# Power_Supply_Board.net
KiCad netlist of a schematic drawn in EAGLE
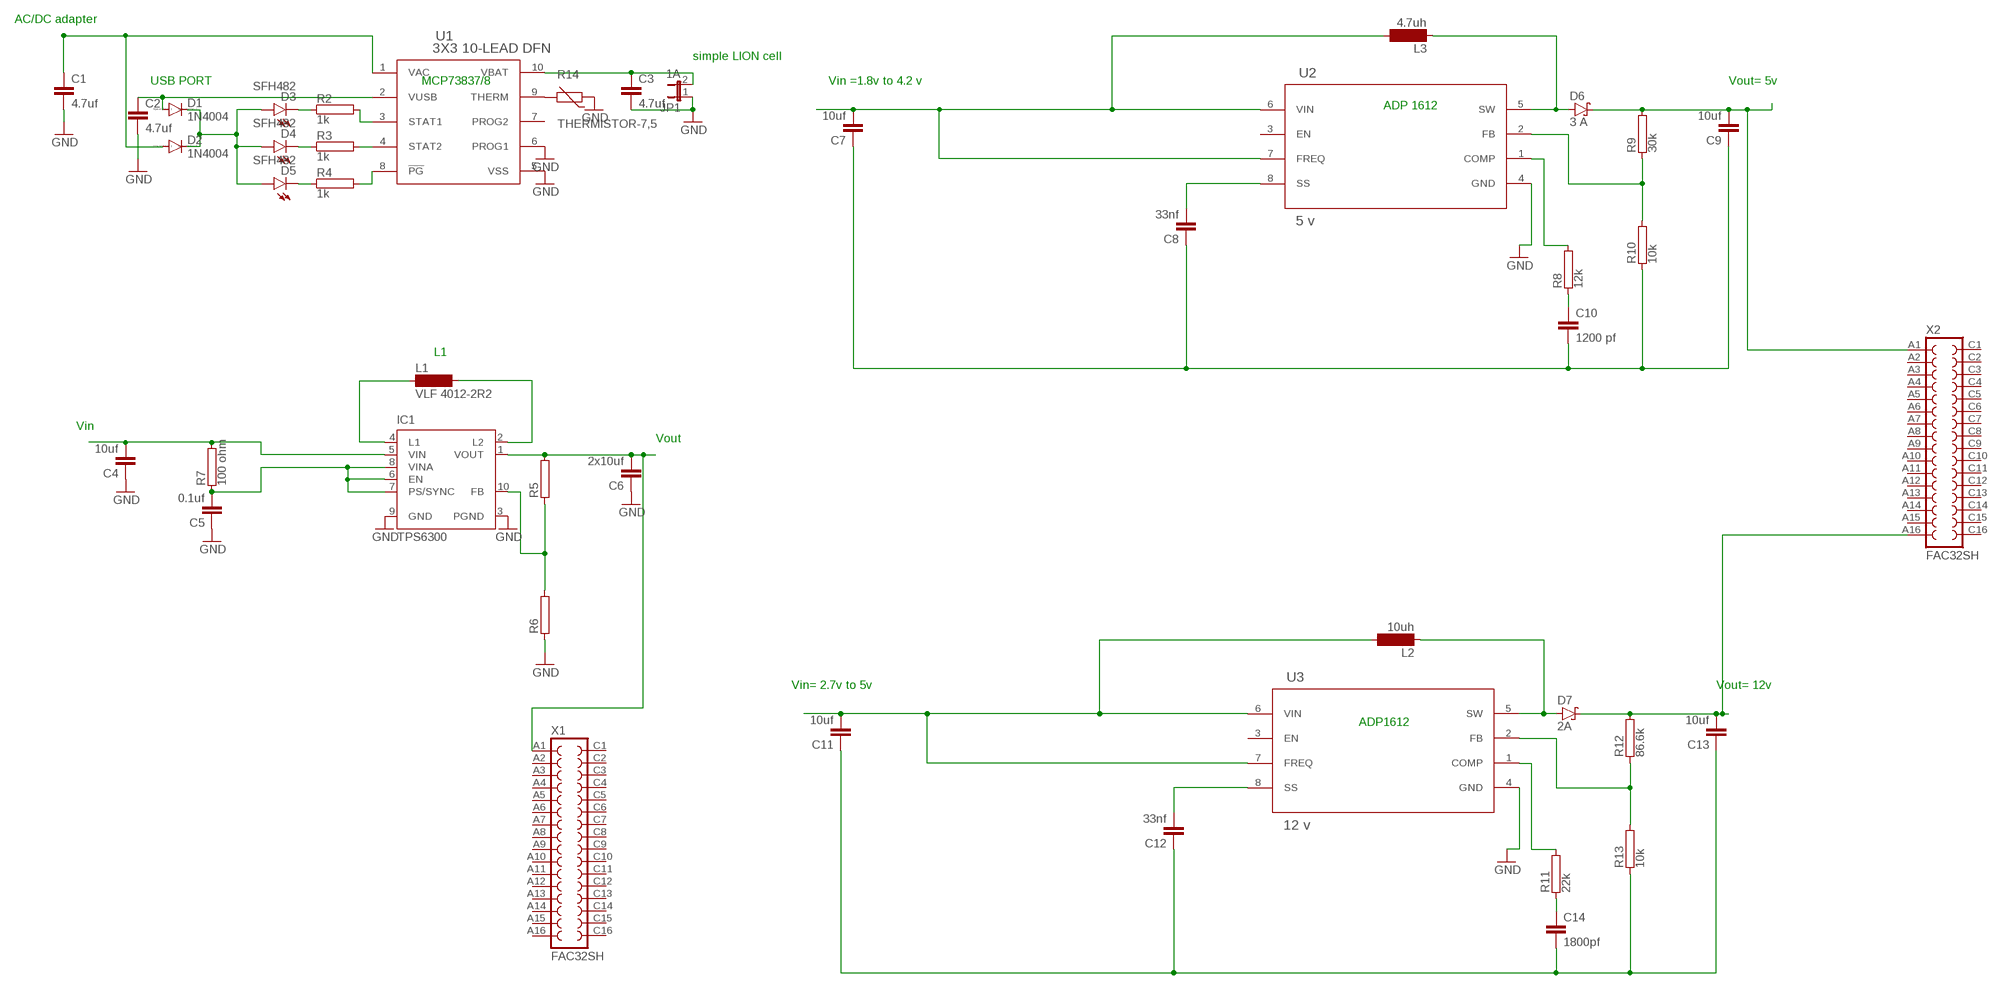
[diagram p0: schematic, sheet 1]

(export (version "E")
  (design (tool "Eeschema 10.0.6"))
  (components
    (comp (ref "C1")
      (value "4.7uf")
      (footprint "eagle-import:C2.5-3")
      (libsource (lib "eagle-import") (part "C2,5-3"))
    )
    (comp (ref "C2")
      (value "4.7uf")
      (footprint "eagle-import:C2.5-3")
      (libsource (lib "eagle-import") (part "C2,5-3"))
    )
    (comp (ref "C3")
      (value "4.7uf")
      (footprint "eagle-import:C2.5-3")
      (libsource (lib "eagle-import") (part "C2,5-3"))
    )
    (comp (ref "C4")
      (value "10uf")
      (footprint "eagle-import:C2.5-3")
      (libsource (lib "eagle-import") (part "C2,5-3"))
    )
    (comp (ref "C5")
      (value "0.1uf")
      (footprint "eagle-import:C2.5-3")
      (libsource (lib "eagle-import") (part "C2,5-3"))
    )
    (comp (ref "C6")
      (value "2x10uf")
      (footprint "eagle-import:C2.5-3")
      (libsource (lib "eagle-import") (part "C2,5-3"))
    )
    (comp (ref "C7")
      (value "10uf")
      (footprint "eagle-import:C2.5-3")
      (libsource (lib "eagle-import") (part "C2,5-3"))
    )
    (comp (ref "C8")
      (value "33nf")
      (footprint "eagle-import:C2.5-3")
      (libsource (lib "eagle-import") (part "C2,5-3"))
    )
    (comp (ref "C9")
      (value "10uf")
      (footprint "eagle-import:C2.5-3")
      (libsource (lib "eagle-import") (part "C2,5-3"))
    )
    (comp (ref "C10")
      (value "1200 pf")
      (footprint "eagle-import:C2.5-3")
      (libsource (lib "eagle-import") (part "C2,5-3"))
    )
    (comp (ref "C11")
      (value "10uf")
      (footprint "eagle-import:C2.5-3")
      (libsource (lib "eagle-import") (part "C2,5-3"))
    )
    (comp (ref "C12")
      (value "33nf")
      (footprint "eagle-import:C2.5-3")
      (libsource (lib "eagle-import") (part "C2,5-3"))
    )
    (comp (ref "C13")
      (value "10uf")
      (footprint "eagle-import:C2.5-3")
      (libsource (lib "eagle-import") (part "C2,5-3"))
    )
    (comp (ref "C14")
      (value "1800pf")
      (footprint "eagle-import:C2.5-3")
      (libsource (lib "eagle-import") (part "C2,5-3"))
    )
    (comp (ref "D1")
      (value "1N4004")
      (footprint "eagle-import:DO41-10")
      (libsource (lib "eagle-import") (part "1N4004"))
    )
    (comp (ref "D2")
      (value "1N4004")
      (footprint "eagle-import:DO41-10")
      (libsource (lib "eagle-import") (part "1N4004"))
    )
    (comp (ref "D3")
      (value "SFH482")
      (footprint "eagle-import:SFH482")
      (libsource (lib "eagle-import") (part "SFH482"))
    )
    (comp (ref "D4")
      (value "SFH482")
      (footprint "eagle-import:SFH482")
      (libsource (lib "eagle-import") (part "SFH482"))
    )
    (comp (ref "D5")
      (value "SFH482")
      (footprint "eagle-import:SFH482")
      (libsource (lib "eagle-import") (part "SFH482"))
    )
    (comp (ref "D6")
      (value "3 A")
      (footprint "eagle-import:C4111-15")
      (libsource (lib "eagle-import") (part "1N5908"))
    )
    (comp (ref "D7")
      (value "2A")
      (footprint "eagle-import:C4111-15")
      (libsource (lib "eagle-import") (part "1N5908"))
    )
    (comp (ref "IC1")
      (value "TPS6300")
      (footprint "eagle-import:DRC-S-PVSON-N10")
      (fields (field (name "MPN") "TPS63000DRCTG4"))
      (libsource (lib "eagle-import") (part "TPS6300"))
    )
    (comp (ref "JP1")
      (value "1A")
      (footprint "eagle-import:JP1")
      (libsource (lib "eagle-import") (part "JP1E"))
    )
    (comp (ref "L1")
      (value "VLF 4012-2R2")
      (footprint "eagle-import:MS85")
      (libsource (lib "eagle-import") (part "MS85"))
    )
    (comp (ref "L2")
      (value "10uh")
      (footprint "eagle-import:MS42")
      (libsource (lib "eagle-import") (part "MS42"))
    )
    (comp (ref "L3")
      (value "4.7uh")
      (footprint "eagle-import:MS42")
      (libsource (lib "eagle-import") (part "MS42"))
    )
    (comp (ref "R2")
      (value "1k")
      (footprint "eagle-import:AC01")
      (libsource (lib "eagle-import") (part "RAC01"))
    )
    (comp (ref "R3")
      (value "1k")
      (footprint "eagle-import:AC01")
      (libsource (lib "eagle-import") (part "RAC01"))
    )
    (comp (ref "R4")
      (value "1k")
      (footprint "eagle-import:AC01")
      (libsource (lib "eagle-import") (part "RAC01"))
    )
    (comp (ref "R5")
      (value "RAC01")
      (footprint "eagle-import:AC01")
      (libsource (lib "eagle-import") (part "RAC01"))
    )
    (comp (ref "R6")
      (value "RAC01")
      (footprint "eagle-import:AC01")
      (libsource (lib "eagle-import") (part "RAC01"))
    )
    (comp (ref "R7")
      (value "100 ohm")
      (footprint "eagle-import:AC01")
      (libsource (lib "eagle-import") (part "RAC01"))
    )
    (comp (ref "R8")
      (value "12k")
      (footprint "eagle-import:AC01")
      (libsource (lib "eagle-import") (part "RAC01"))
    )
    (comp (ref "R9")
      (value "30k")
      (footprint "eagle-import:AC01")
      (libsource (lib "eagle-import") (part "RAC01"))
    )
    (comp (ref "R10")
      (value "10k")
      (footprint "eagle-import:AC01")
      (libsource (lib "eagle-import") (part "RAC01"))
    )
    (comp (ref "R11")
      (value "22k")
      (footprint "eagle-import:AC01")
      (libsource (lib "eagle-import") (part "RAC01"))
    )
    (comp (ref "R12")
      (value "86.6k")
      (footprint "eagle-import:AC01")
      (libsource (lib "eagle-import") (part "RAC01"))
    )
    (comp (ref "R13")
      (value "10k")
      (footprint "eagle-import:AC01")
      (libsource (lib "eagle-import") (part "RAC01"))
    )
    (comp (ref "R14")
      (value "THERMISTOR-7,5")
      (footprint "eagle-import:R-7,5")
      (libsource (lib "eagle-import") (part "THERMISTOR-7,5"))
    )
    (comp (ref "U1")
      (value "3X3 10-LEAD DFN")
      (footprint "eagle-import:MSOP10_MC_MCH")
      (fields (field (name "MANUFACTURER_PART_NUMBER") "MCP73837-FCI/UN"))
      (libsource (lib "eagle-import") (part "MCP73837-FCI/UN"))
    )
    (comp (ref "U2")
      (value "5 v")
      (footprint "eagle-import:RM_8_ADI")
      (fields (field (name "MANUFACTURER_PART_NUMBER") "ADP1612ARMZ-R7"))
      (libsource (lib "eagle-import") (part "ADP1612"))
    )
    (comp (ref "U3")
      (value "12 v")
      (footprint "eagle-import:RM_8_ADI")
      (fields (field (name "MANUFACTURER_PART_NUMBER") "ADP1612ARMZ-R7"))
      (libsource (lib "eagle-import") (part "ADP1612"))
    )
    (comp (ref "X1")
      (value "FAC32SH")
      (footprint "eagle-import:FAC32SH")
      (libsource (lib "eagle-import") (part "FAC32SH"))
    )
    (comp (ref "X2")
      (value "FAC32SH")
      (footprint "eagle-import:FAC32SH")
      (libsource (lib "eagle-import") (part "FAC32SH"))
    )
  )
  (nets
    (net (code "1") (name "GND") (class "Default")
      (node (ref "C1") (pin "2") (pinfunction "2_2") (pintype "passive"))
      (node (ref "C2") (pin "2") (pinfunction "2_2") (pintype "passive"))
      (node (ref "C3") (pin "2") (pinfunction "2_2") (pintype "passive"))
      (node (ref "C4") (pin "1") (pinfunction "1_1") (pintype "passive"))
      (node (ref "C5") (pin "1") (pinfunction "1_1") (pintype "passive"))
      (node (ref "C6") (pin "1") (pinfunction "1_1") (pintype "passive"))
      (node (ref "IC1") (pin "3") (pinfunction "PGND_3") (pintype "power_in"))
      (node (ref "IC1") (pin "9") (pinfunction "GND_9") (pintype "power_in"))
      (node (ref "JP1") (pin "1") (pinfunction "1_1") (pintype "passive"))
      (node (ref "R14") (pin "1") (pinfunction "1_1") (pintype "passive"))
      (node (ref "R6") (pin "1") (pinfunction "1_1") (pintype "passive"))
      (node (ref "U1") (pin "5") (pinfunction "VSS_5") (pintype "passive"))
      (node (ref "U1") (pin "6") (pinfunction "PROG1_6") (pintype "passive"))
      (node (ref "U2") (pin "4") (pinfunction "GND_4") (pintype "passive"))
      (node (ref "U3") (pin "4") (pinfunction "GND_4") (pintype "passive"))
    )
    (net (code "2") (name "Net-(C9-Pad2)") (class "Default")
      (node (ref "C9") (pin "2") (pinfunction "2_2") (pintype "passive"))
      (node (ref "D6") (pin "C") (pinfunction "C_C") (pintype "passive"))
      (node (ref "R9") (pin "2") (pinfunction "2_2") (pintype "passive"))
      (node (ref "X2") (pin "A1") (pinfunction "A1_A1") (pintype "passive"))
    )
    (net (code "3") (name "Net-(C10-Pad1)") (class "Default")
      (node (ref "C10") (pin "1") (pinfunction "1_1") (pintype "passive"))
      (node (ref "R8") (pin "1") (pinfunction "1_1") (pintype "passive"))
    )
    (net (code "4") (name "Net-(C10-Pad2)") (class "Default")
      (node (ref "C10") (pin "2") (pinfunction "2_2") (pintype "passive"))
      (node (ref "C7") (pin "1") (pinfunction "1_1") (pintype "passive"))
      (node (ref "C8") (pin "1") (pinfunction "1_1") (pintype "passive"))
      (node (ref "C9") (pin "1") (pinfunction "1_1") (pintype "passive"))
      (node (ref "R10") (pin "1") (pinfunction "1_1") (pintype "passive"))
    )
    (net (code "5") (name "Net-(C11-Pad1)") (class "Default")
      (node (ref "C11") (pin "1") (pinfunction "1_1") (pintype "passive"))
      (node (ref "C12") (pin "1") (pinfunction "1_1") (pintype "passive"))
      (node (ref "C13") (pin "1") (pinfunction "1_1") (pintype "passive"))
      (node (ref "C14") (pin "2") (pinfunction "2_2") (pintype "passive"))
      (node (ref "R13") (pin "1") (pinfunction "1_1") (pintype "passive"))
    )
    (net (code "6") (name "Net-(C13-Pad2)") (class "Default")
      (node (ref "C13") (pin "2") (pinfunction "2_2") (pintype "passive"))
      (node (ref "D7") (pin "C") (pinfunction "C_C") (pintype "passive"))
      (node (ref "R12") (pin "2") (pinfunction "2_2") (pintype "passive"))
      (node (ref "X2") (pin "A16") (pinfunction "A16_A16") (pintype "passive"))
    )
    (net (code "7") (name "Net-(C14-Pad1)") (class "Default")
      (node (ref "C14") (pin "1") (pinfunction "1_1") (pintype "passive"))
      (node (ref "R11") (pin "1") (pinfunction "1_1") (pintype "passive"))
    )
    (net (code "8") (name "Net-(D1-PadC)") (class "Default")
      (node (ref "D1") (pin "C") (pinfunction "C_C") (pintype "passive"))
      (node (ref "D2") (pin "C") (pinfunction "C_C") (pintype "passive"))
      (node (ref "D3") (pin "A") (pinfunction "A_A") (pintype "passive"))
      (node (ref "D4") (pin "A") (pinfunction "A_A") (pintype "passive"))
      (node (ref "D5") (pin "A") (pinfunction "A_A") (pintype "passive"))
    )
    (net (code "9") (name "Net-(D3-C)") (class "Default")
      (node (ref "D3") (pin "K") (pinfunction "C_K") (pintype "passive"))
      (node (ref "R2") (pin "1") (pinfunction "1_1") (pintype "passive"))
    )
    (net (code "10") (name "Net-(D4-C)") (class "Default")
      (node (ref "D4") (pin "K") (pinfunction "C_K") (pintype "passive"))
      (node (ref "R3") (pin "1") (pinfunction "1_1") (pintype "passive"))
    )
    (net (code "11") (name "Net-(D5-C)") (class "Default")
      (node (ref "D5") (pin "K") (pinfunction "C_K") (pintype "passive"))
      (node (ref "R4") (pin "1") (pinfunction "1_1") (pintype "passive"))
    )
    (net (code "12") (name "Net-(IC1A-EN)") (class "Default")
      (node (ref "C5") (pin "2") (pinfunction "2_2") (pintype "passive"))
      (node (ref "IC1") (pin "6") (pinfunction "EN_6") (pintype "input"))
      (node (ref "IC1") (pin "7") (pinfunction "PS/SYNC_7") (pintype "input"))
      (node (ref "IC1") (pin "8") (pinfunction "VINA_8") (pintype "input"))
      (node (ref "R7") (pin "1") (pinfunction "1_1") (pintype "passive"))
    )
    (net (code "13") (name "Net-(IC1A-FB)") (class "Default")
      (node (ref "IC1") (pin "10") (pinfunction "FB_10") (pintype "input"))
      (node (ref "R5") (pin "1") (pinfunction "1_1") (pintype "passive"))
      (node (ref "R6") (pin "2") (pinfunction "2_2") (pintype "passive"))
    )
    (net (code "14") (name "Net-(IC1A-L1)") (class "Default")
      (node (ref "IC1") (pin "4") (pinfunction "L1_4") (pintype "passive"))
      (node (ref "L1") (pin "1") (pinfunction "1_1") (pintype "passive"))
    )
    (net (code "15") (name "Net-(IC1A-L2)") (class "Default")
      (node (ref "IC1") (pin "2") (pinfunction "L2_2") (pintype "passive"))
      (node (ref "L1") (pin "2") (pinfunction "2_2") (pintype "passive"))
    )
    (net (code "16") (name "Net-(IC1A-VIN)") (class "Default")
      (node (ref "C4") (pin "2") (pinfunction "2_2") (pintype "passive"))
      (node (ref "IC1") (pin "5") (pinfunction "VIN_5") (pintype "input"))
      (node (ref "R7") (pin "2") (pinfunction "2_2") (pintype "passive"))
    )
    (net (code "17") (name "Net-(IC1A-VOUT)") (class "Default")
      (node (ref "C6") (pin "2") (pinfunction "2_2") (pintype "passive"))
      (node (ref "IC1") (pin "1") (pinfunction "VOUT_1") (pintype "output"))
      (node (ref "R5") (pin "2") (pinfunction "2_2") (pintype "passive"))
      (node (ref "X1") (pin "A1") (pinfunction "A1_A1") (pintype "passive"))
    )
    (net (code "18") (name "Net-(U1-STAT1)") (class "Default")
      (node (ref "R2") (pin "2") (pinfunction "2_2") (pintype "passive"))
      (node (ref "U1") (pin "3") (pinfunction "STAT1_3") (pintype "passive"))
    )
    (net (code "19") (name "Net-(U1-STAT2)") (class "Default")
      (node (ref "R3") (pin "2") (pinfunction "2_2") (pintype "passive"))
      (node (ref "U1") (pin "4") (pinfunction "STAT2_4") (pintype "passive"))
    )
    (net (code "20") (name "Net-(U1-THERM)") (class "Default")
      (node (ref "R14") (pin "2") (pinfunction "2_2") (pintype "passive"))
      (node (ref "U1") (pin "9") (pinfunction "THERM_9") (pintype "passive"))
    )
    (net (code "21") (name "Net-(U1-VAC)") (class "Default")
      (node (ref "C1") (pin "1") (pinfunction "1_1") (pintype "passive"))
      (node (ref "D2") (pin "A") (pinfunction "A_A") (pintype "passive"))
      (node (ref "U1") (pin "1") (pinfunction "VAC_1") (pintype "passive"))
    )
    (net (code "22") (name "Net-(U1-VBAT)") (class "Default")
      (node (ref "C3") (pin "1") (pinfunction "1_1") (pintype "passive"))
      (node (ref "JP1") (pin "2") (pinfunction "2_2") (pintype "passive"))
      (node (ref "U1") (pin "10") (pinfunction "VBAT_10") (pintype "passive"))
    )
    (net (code "23") (name "Net-(U1-VUSB)") (class "Default")
      (node (ref "C2") (pin "1") (pinfunction "1_1") (pintype "passive"))
      (node (ref "D1") (pin "A") (pinfunction "A_A") (pintype "passive"))
      (node (ref "U1") (pin "2") (pinfunction "VUSB_2") (pintype "passive"))
    )
    (net (code "24") (name "Net-(U1-~{PG})") (class "Default")
      (node (ref "R4") (pin "2") (pinfunction "2_2") (pintype "passive"))
      (node (ref "U1") (pin "8") (pinfunction "~{PG}_8") (pintype "passive"))
    )
    (net (code "25") (name "Net-(U2-COMP)") (class "Default")
      (node (ref "R8") (pin "2") (pinfunction "2_2") (pintype "passive"))
      (node (ref "U2") (pin "1") (pinfunction "COMP_1") (pintype "passive"))
    )
    (net (code "26") (name "Net-(U2-FB)") (class "Default")
      (node (ref "R10") (pin "2") (pinfunction "2_2") (pintype "passive"))
      (node (ref "R9") (pin "1") (pinfunction "1_1") (pintype "passive"))
      (node (ref "U2") (pin "2") (pinfunction "FB_2") (pintype "passive"))
    )
    (net (code "27") (name "Net-(U2-FREQ)") (class "Default")
      (node (ref "C7") (pin "2") (pinfunction "2_2") (pintype "passive"))
      (node (ref "L3") (pin "2") (pinfunction "2_2") (pintype "passive"))
      (node (ref "U2") (pin "6") (pinfunction "VIN_6") (pintype "passive"))
      (node (ref "U2") (pin "7") (pinfunction "FREQ_7") (pintype "passive"))
    )
    (net (code "28") (name "Net-(U2-SS)") (class "Default")
      (node (ref "C8") (pin "2") (pinfunction "2_2") (pintype "passive"))
      (node (ref "U2") (pin "8") (pinfunction "SS_8") (pintype "passive"))
    )
    (net (code "29") (name "Net-(U2-SW)") (class "Default")
      (node (ref "D6") (pin "A") (pinfunction "A_A") (pintype "passive"))
      (node (ref "L3") (pin "1") (pinfunction "1_1") (pintype "passive"))
      (node (ref "U2") (pin "5") (pinfunction "SW_5") (pintype "passive"))
    )
    (net (code "30") (name "Net-(U3-COMP)") (class "Default")
      (node (ref "R11") (pin "2") (pinfunction "2_2") (pintype "passive"))
      (node (ref "U3") (pin "1") (pinfunction "COMP_1") (pintype "passive"))
    )
    (net (code "31") (name "Net-(U3-FB)") (class "Default")
      (node (ref "R12") (pin "1") (pinfunction "1_1") (pintype "passive"))
      (node (ref "R13") (pin "2") (pinfunction "2_2") (pintype "passive"))
      (node (ref "U3") (pin "2") (pinfunction "FB_2") (pintype "passive"))
    )
    (net (code "32") (name "Net-(U3-FREQ)") (class "Default")
      (node (ref "C11") (pin "2") (pinfunction "2_2") (pintype "passive"))
      (node (ref "L2") (pin "2") (pinfunction "2_2") (pintype "passive"))
      (node (ref "U3") (pin "6") (pinfunction "VIN_6") (pintype "passive"))
      (node (ref "U3") (pin "7") (pinfunction "FREQ_7") (pintype "passive"))
    )
    (net (code "33") (name "Net-(U3-SS)") (class "Default")
      (node (ref "C12") (pin "2") (pinfunction "2_2") (pintype "passive"))
      (node (ref "U3") (pin "8") (pinfunction "SS_8") (pintype "passive"))
    )
    (net (code "34") (name "Net-(U3-SW)") (class "Default")
      (node (ref "D7") (pin "A") (pinfunction "A_A") (pintype "passive"))
      (node (ref "L2") (pin "1") (pinfunction "1_1") (pintype "passive"))
      (node (ref "U3") (pin "5") (pinfunction "SW_5") (pintype "passive"))
    )
    (net (code "35") (name "unconnected-(U1-PROG2-Pad7)") (class "Default")
      (node (ref "U1") (pin "7") (pinfunction "PROG2_7") (pintype "passive"))
    )
    (net (code "36") (name "unconnected-(U2-EN-Pad3)") (class "Default")
      (node (ref "U2") (pin "3") (pinfunction "EN_3") (pintype "passive"))
    )
    (net (code "37") (name "unconnected-(U3-EN-Pad3)") (class "Default")
      (node (ref "U3") (pin "3") (pinfunction "EN_3") (pintype "passive"))
    )
    (net (code "38") (name "unconnected-(X1-PadA2)") (class "Default")
      (node (ref "X1") (pin "A2") (pinfunction "A2_A2") (pintype "passive"))
    )
    (net (code "39") (name "unconnected-(X1-PadA3)") (class "Default")
      (node (ref "X1") (pin "A3") (pinfunction "A3_A3") (pintype "passive"))
    )
    (net (code "40") (name "unconnected-(X1-PadA4)") (class "Default")
      (node (ref "X1") (pin "A4") (pinfunction "A4_A4") (pintype "passive"))
    )
    (net (code "41") (name "unconnected-(X1-PadA5)") (class "Default")
      (node (ref "X1") (pin "A5") (pinfunction "A5_A5") (pintype "passive"))
    )
    (net (code "42") (name "unconnected-(X1-PadA6)") (class "Default")
      (node (ref "X1") (pin "A6") (pinfunction "A6_A6") (pintype "passive"))
    )
    (net (code "43") (name "unconnected-(X1-PadA7)") (class "Default")
      (node (ref "X1") (pin "A7") (pinfunction "A7_A7") (pintype "passive"))
    )
    (net (code "44") (name "unconnected-(X1-PadA8)") (class "Default")
      (node (ref "X1") (pin "A8") (pinfunction "A8_A8") (pintype "passive"))
    )
    (net (code "45") (name "unconnected-(X1-PadA9)") (class "Default")
      (node (ref "X1") (pin "A9") (pinfunction "A9_A9") (pintype "passive"))
    )
    (net (code "46") (name "unconnected-(X1-PadA10)") (class "Default")
      (node (ref "X1") (pin "A10") (pinfunction "A10_A10") (pintype "passive"))
    )
    (net (code "47") (name "unconnected-(X1-PadA11)") (class "Default")
      (node (ref "X1") (pin "A11") (pinfunction "A11_A11") (pintype "passive"))
    )
    (net (code "48") (name "unconnected-(X1-PadA12)") (class "Default")
      (node (ref "X1") (pin "A12") (pinfunction "A12_A12") (pintype "passive"))
    )
    (net (code "49") (name "unconnected-(X1-PadA13)") (class "Default")
      (node (ref "X1") (pin "A13") (pinfunction "A13_A13") (pintype "passive"))
    )
    (net (code "50") (name "unconnected-(X1-PadA14)") (class "Default")
      (node (ref "X1") (pin "A14") (pinfunction "A14_A14") (pintype "passive"))
    )
    (net (code "51") (name "unconnected-(X1-PadA15)") (class "Default")
      (node (ref "X1") (pin "A15") (pinfunction "A15_A15") (pintype "passive"))
    )
    (net (code "52") (name "unconnected-(X1-PadA16)") (class "Default")
      (node (ref "X1") (pin "A16") (pinfunction "A16_A16") (pintype "passive"))
    )
    (net (code "53") (name "unconnected-(X1-PadC1)") (class "Default")
      (node (ref "X1") (pin "C1") (pinfunction "C1_C1") (pintype "passive"))
    )
    (net (code "54") (name "unconnected-(X1-PadC2)") (class "Default")
      (node (ref "X1") (pin "C2") (pinfunction "C2_C2") (pintype "passive"))
    )
    (net (code "55") (name "unconnected-(X1-PadC3)") (class "Default")
      (node (ref "X1") (pin "C3") (pinfunction "C3_C3") (pintype "passive"))
    )
    (net (code "56") (name "unconnected-(X1-PadC4)") (class "Default")
      (node (ref "X1") (pin "C4") (pinfunction "C4_C4") (pintype "passive"))
    )
    (net (code "57") (name "unconnected-(X1-PadC5)") (class "Default")
      (node (ref "X1") (pin "C5") (pinfunction "C5_C5") (pintype "passive"))
    )
    (net (code "58") (name "unconnected-(X1-PadC6)") (class "Default")
      (node (ref "X1") (pin "C6") (pinfunction "C6_C6") (pintype "passive"))
    )
    (net (code "59") (name "unconnected-(X1-PadC7)") (class "Default")
      (node (ref "X1") (pin "C7") (pinfunction "C7_C7") (pintype "passive"))
    )
    (net (code "60") (name "unconnected-(X1-PadC8)") (class "Default")
      (node (ref "X1") (pin "C8") (pinfunction "C8_C8") (pintype "passive"))
    )
    (net (code "61") (name "unconnected-(X1-PadC9)") (class "Default")
      (node (ref "X1") (pin "C9") (pinfunction "C9_C9") (pintype "passive"))
    )
    (net (code "62") (name "unconnected-(X1-PadC10)") (class "Default")
      (node (ref "X1") (pin "C10") (pinfunction "C10_C10") (pintype "passive"))
    )
    (net (code "63") (name "unconnected-(X1-PadC11)") (class "Default")
      (node (ref "X1") (pin "C11") (pinfunction "C11_C11") (pintype "passive"))
    )
    (net (code "64") (name "unconnected-(X1-PadC12)") (class "Default")
      (node (ref "X1") (pin "C12") (pinfunction "C12_C12") (pintype "passive"))
    )
    (net (code "65") (name "unconnected-(X1-PadC13)") (class "Default")
      (node (ref "X1") (pin "C13") (pinfunction "C13_C13") (pintype "passive"))
    )
    (net (code "66") (name "unconnected-(X1-PadC14)") (class "Default")
      (node (ref "X1") (pin "C14") (pinfunction "C14_C14") (pintype "passive"))
    )
    (net (code "67") (name "unconnected-(X1-PadC15)") (class "Default")
      (node (ref "X1") (pin "C15") (pinfunction "C15_C15") (pintype "passive"))
    )
    (net (code "68") (name "unconnected-(X1-PadC16)") (class "Default")
      (node (ref "X1") (pin "C16") (pinfunction "C16_C16") (pintype "passive"))
    )
    (net (code "69") (name "unconnected-(X2-PadA2)") (class "Default")
      (node (ref "X2") (pin "A2") (pinfunction "A2_A2") (pintype "passive"))
    )
    (net (code "70") (name "unconnected-(X2-PadA3)") (class "Default")
      (node (ref "X2") (pin "A3") (pinfunction "A3_A3") (pintype "passive"))
    )
    (net (code "71") (name "unconnected-(X2-PadA4)") (class "Default")
      (node (ref "X2") (pin "A4") (pinfunction "A4_A4") (pintype "passive"))
    )
    (net (code "72") (name "unconnected-(X2-PadA5)") (class "Default")
      (node (ref "X2") (pin "A5") (pinfunction "A5_A5") (pintype "passive"))
    )
    (net (code "73") (name "unconnected-(X2-PadA6)") (class "Default")
      (node (ref "X2") (pin "A6") (pinfunction "A6_A6") (pintype "passive"))
    )
    (net (code "74") (name "unconnected-(X2-PadA7)") (class "Default")
      (node (ref "X2") (pin "A7") (pinfunction "A7_A7") (pintype "passive"))
    )
    (net (code "75") (name "unconnected-(X2-PadA8)") (class "Default")
      (node (ref "X2") (pin "A8") (pinfunction "A8_A8") (pintype "passive"))
    )
    (net (code "76") (name "unconnected-(X2-PadA9)") (class "Default")
      (node (ref "X2") (pin "A9") (pinfunction "A9_A9") (pintype "passive"))
    )
    (net (code "77") (name "unconnected-(X2-PadA10)") (class "Default")
      (node (ref "X2") (pin "A10") (pinfunction "A10_A10") (pintype "passive"))
    )
    (net (code "78") (name "unconnected-(X2-PadA11)") (class "Default")
      (node (ref "X2") (pin "A11") (pinfunction "A11_A11") (pintype "passive"))
    )
    (net (code "79") (name "unconnected-(X2-PadA12)") (class "Default")
      (node (ref "X2") (pin "A12") (pinfunction "A12_A12") (pintype "passive"))
    )
    (net (code "80") (name "unconnected-(X2-PadA13)") (class "Default")
      (node (ref "X2") (pin "A13") (pinfunction "A13_A13") (pintype "passive"))
    )
    (net (code "81") (name "unconnected-(X2-PadA14)") (class "Default")
      (node (ref "X2") (pin "A14") (pinfunction "A14_A14") (pintype "passive"))
    )
    (net (code "82") (name "unconnected-(X2-PadA15)") (class "Default")
      (node (ref "X2") (pin "A15") (pinfunction "A15_A15") (pintype "passive"))
    )
    (net (code "83") (name "unconnected-(X2-PadC1)") (class "Default")
      (node (ref "X2") (pin "C1") (pinfunction "C1_C1") (pintype "passive"))
    )
    (net (code "84") (name "unconnected-(X2-PadC2)") (class "Default")
      (node (ref "X2") (pin "C2") (pinfunction "C2_C2") (pintype "passive"))
    )
    (net (code "85") (name "unconnected-(X2-PadC3)") (class "Default")
      (node (ref "X2") (pin "C3") (pinfunction "C3_C3") (pintype "passive"))
    )
    (net (code "86") (name "unconnected-(X2-PadC4)") (class "Default")
      (node (ref "X2") (pin "C4") (pinfunction "C4_C4") (pintype "passive"))
    )
    (net (code "87") (name "unconnected-(X2-PadC5)") (class "Default")
      (node (ref "X2") (pin "C5") (pinfunction "C5_C5") (pintype "passive"))
    )
    (net (code "88") (name "unconnected-(X2-PadC6)") (class "Default")
      (node (ref "X2") (pin "C6") (pinfunction "C6_C6") (pintype "passive"))
    )
    (net (code "89") (name "unconnected-(X2-PadC7)") (class "Default")
      (node (ref "X2") (pin "C7") (pinfunction "C7_C7") (pintype "passive"))
    )
    (net (code "90") (name "unconnected-(X2-PadC8)") (class "Default")
      (node (ref "X2") (pin "C8") (pinfunction "C8_C8") (pintype "passive"))
    )
    (net (code "91") (name "unconnected-(X2-PadC9)") (class "Default")
      (node (ref "X2") (pin "C9") (pinfunction "C9_C9") (pintype "passive"))
    )
    (net (code "92") (name "unconnected-(X2-PadC10)") (class "Default")
      (node (ref "X2") (pin "C10") (pinfunction "C10_C10") (pintype "passive"))
    )
    (net (code "93") (name "unconnected-(X2-PadC11)") (class "Default")
      (node (ref "X2") (pin "C11") (pinfunction "C11_C11") (pintype "passive"))
    )
    (net (code "94") (name "unconnected-(X2-PadC12)") (class "Default")
      (node (ref "X2") (pin "C12") (pinfunction "C12_C12") (pintype "passive"))
    )
    (net (code "95") (name "unconnected-(X2-PadC13)") (class "Default")
      (node (ref "X2") (pin "C13") (pinfunction "C13_C13") (pintype "passive"))
    )
    (net (code "96") (name "unconnected-(X2-PadC14)") (class "Default")
      (node (ref "X2") (pin "C14") (pinfunction "C14_C14") (pintype "passive"))
    )
    (net (code "97") (name "unconnected-(X2-PadC15)") (class "Default")
      (node (ref "X2") (pin "C15") (pinfunction "C15_C15") (pintype "passive"))
    )
    (net (code "98") (name "unconnected-(X2-PadC16)") (class "Default")
      (node (ref "X2") (pin "C16") (pinfunction "C16_C16") (pintype "passive"))
    )
  )
)
